# boost.net
KiCad netlist of a schematic drawn in Altium Designer
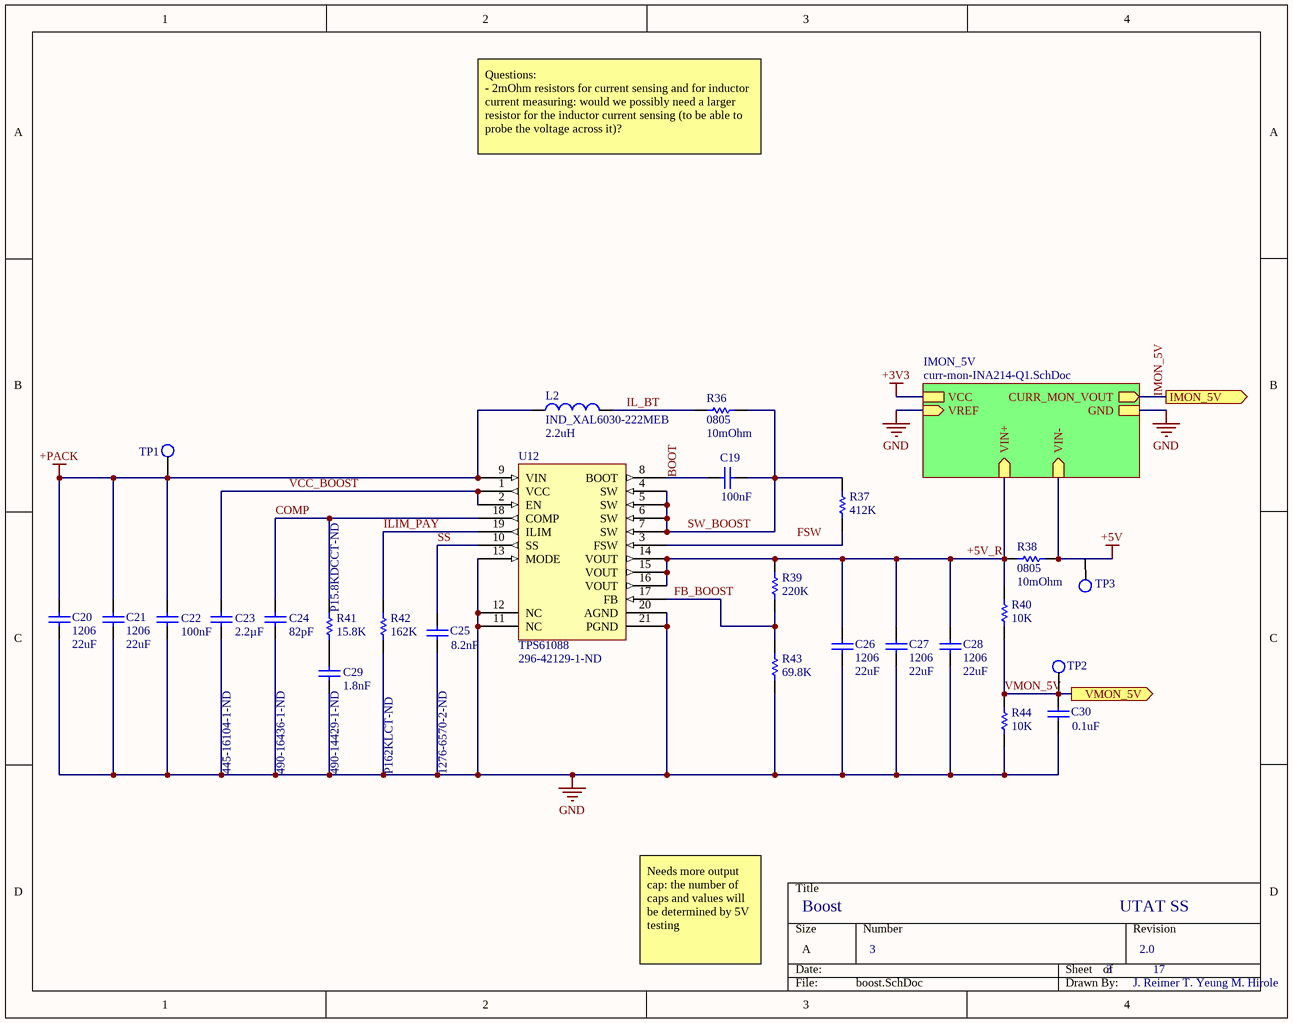
[diagram p0: boost.SchDoc]

(export (version "E")
  (design (tool "Eeschema 10.0.6"))
  (components
    (comp (ref "C19")
      (value "100nF")
      (footprint "CAP0402R")
      (description "0402 capacitor")
      (fields (field (name "Comment") "0402"))
      (libsource (lib "heron-general") (part "CAP0402"))
    )
    (comp (ref "C20")
      (value "1206")
      (footprint "CAP1206R")
      (description "1206 capacitor")
      (fields (field (name "ALTIUM_VALUE") "22uF"))
      (libsource (lib "heron-general") (part "CAP1206"))
    )
    (comp (ref "C21")
      (value "1206")
      (footprint "CAP1206R")
      (description "1206 capacitor")
      (fields (field (name "ALTIUM_VALUE") "22uF"))
      (libsource (lib "heron-general") (part "CAP1206"))
    )
    (comp (ref "C22")
      (value "100nF")
      (footprint "CAP0402R")
      (description "0402 capacitor")
      (fields (field (name "Comment") "0402"))
      (libsource (lib "heron-general") (part "CAP0402"))
    )
    (comp (ref "C23")
      (value "2.2µF")
      (footprint "CAP0603R")
      (description "0603 capacitor")
      (fields
        (field (name "SUPPLIER PART NUMBER 1") "445-16104-1-ND")
        (field (name "MANUFACTURER") "TDK")
        (field (name "MANUFACTURER PART NUMBER") "CGA3E1X7S1C225K080AC")
      )
      (libsource (lib "heron-general") (part "CAP0603"))
    )
    (comp (ref "C24")
      (value "82pF")
      (footprint "CAP0402R")
      (description "0402 capacitor")
      (fields
        (field (name "SUPPLIER PART NUMBER 1") "490-16436-1-ND")
        (field (name "MANUFACTURER") "Murata")
        (field (name "MANUFACTURER PART NUMBER") "GCM1555C1H820FA16D")
      )
      (libsource (lib "heron-general") (part "CAP0402"))
    )
    (comp (ref "C25")
      (value "8.2nF")
      (footprint "CAP0402R")
      (description "0402 capacitor")
      (fields
        (field (name "SUPPLIER PART NUMBER 1") "1276-6570-2-ND")
        (field (name "MANUFACTURER") "Samsung")
        (field (name "MANUFACTURER PART NUMBER") "CL05B822KB5VPNC")
      )
      (libsource (lib "heron-general") (part "CAP0402"))
    )
    (comp (ref "C26")
      (value "1206")
      (footprint "CAP1206R")
      (description "1206 capacitor")
      (fields (field (name "ALTIUM_VALUE") "22uF"))
      (libsource (lib "heron-general") (part "CAP1206"))
    )
    (comp (ref "C27")
      (value "1206")
      (footprint "CAP1206R")
      (description "1206 capacitor")
      (fields (field (name "ALTIUM_VALUE") "22uF"))
      (libsource (lib "heron-general") (part "CAP1206"))
    )
    (comp (ref "C28")
      (value "1206")
      (footprint "CAP1206R")
      (description "1206 capacitor")
      (fields (field (name "ALTIUM_VALUE") "22uF"))
      (libsource (lib "heron-general") (part "CAP1206"))
    )
    (comp (ref "C29")
      (value "1.8nF")
      (footprint "CAP0402R")
      (description "0402 capacitor")
      (fields
        (field (name "SUPPLIER PART NUMBER 1") "490-14429-1-ND")
        (field (name "MANUFACTURER") "Murata")
        (field (name "MANUFACTURER PART NUMBER") "GCM155R71H182KA37D")
      )
      (libsource (lib "heron-general") (part "CAP0402"))
    )
    (comp (ref "C30")
      (value "0.1uF")
      (footprint "CAP0402R")
      (description "0402 capacitor")
      (fields (field (name "Comment") "0402"))
      (libsource (lib "heron-general") (part "CAP0402"))
    )
    (comp (ref "L2")
      (value "IND_XAL6030-222MEB")
      (footprint "XAL6030-222MEB")
      (description "Inductor")
      (fields
        (field (name "MANUFACTURER") "Coilcraft")
        (field (name "MANUFACTURER PART NUMBER") "XAL6030-222MEB")
        (field (name "ALTIUM_VALUE") "2.2uH")
        (field (name "PUBLISHER") "Altium Limited")
      )
      (libsource (lib "heron-general") (part "IND_XAL6030-222MEB"))
    )
    (comp (ref "R36")
      (value "0805")
      (footprint "RES0805R")
      (description "0805 resistor")
      (fields
        (field (name "ALTIUM_VALUE") "10mOhm")
        (field (name "MANUFACTURER") "Panasonic")
        (field (name "MANUFACTURER PART NUMBER") "ERJ-8BWJR010V")
      )
      (libsource (lib "heron-general") (part "RES0805"))
    )
    (comp (ref "R37")
      (value "412K")
      (footprint "RES0402R")
      (description "0402 resistor")
      (fields (field (name "Comment") "0402"))
      (libsource (lib "heron-general") (part "RES0402"))
    )
    (comp (ref "R38")
      (value "0805")
      (footprint "RES0805R")
      (description "0805 resistor")
      (fields
        (field (name "ALTIUM_VALUE") "10mOhm")
        (field (name "MANUFACTURER") "Panasonic")
        (field (name "MANUFACTURER PART NUMBER") "ERJ-8BWJR010V")
      )
      (libsource (lib "heron-general") (part "RES0805"))
    )
    (comp (ref "R39")
      (value "220K")
      (footprint "RES0402R")
      (description "0402 resistor")
      (fields (field (name "Comment") "0402"))
      (libsource (lib "heron-general") (part "RES0402"))
    )
    (comp (ref "R40")
      (value "10K")
      (footprint "RES0402R")
      (description "0402 resistor")
      (fields (field (name "Comment") "0402"))
      (libsource (lib "heron-general") (part "RES0402"))
    )
    (comp (ref "R41")
      (value "15.8K")
      (footprint "RES0402R")
      (description "0402 resistor")
      (fields
        (field (name "SUPPLIER PART NUMBER 1") "P15.8KDCCT-ND")
        (field (name "MANUFACTURER") "Panasonic")
        (field (name "MANUFACTURER PART NUMBER") "ERA-2AEB1582X")
      )
      (libsource (lib "heron-general") (part "RES0402"))
    )
    (comp (ref "R42")
      (value "162K")
      (footprint "RES0402R")
      (description "0402 resistor")
      (fields
        (field (name "SUPPLIER PART NUMBER 1") "P162KLCT-ND")
        (field (name "MANUFACTURER") "Panasonic")
        (field (name "MANUFACTURER PART NUMBER") "ERJ-2RKF1623X")
      )
      (libsource (lib "heron-general") (part "RES0402"))
    )
    (comp (ref "R43")
      (value "69.8K")
      (footprint "RES0402R")
      (description "0402 resistor")
      (fields (field (name "Comment") "0402"))
      (libsource (lib "heron-general") (part "RES0402"))
    )
    (comp (ref "R44")
      (value "10K")
      (footprint "RES0402R")
      (description "0402 resistor")
      (fields (field (name "Comment") "0402"))
      (libsource (lib "heron-general") (part "RES0402"))
    )
    (comp (ref "U12")
      (value "TPS61088")
      (footprint "QFN50P450X350X100-21N")
      (description "Boost converter")
      (fields (field (name "SUPPLIER PART NUMBER 1") "296-42129-1-ND"))
      (libsource (lib "heron-general") (part "TPS61088"))
    )
  )
  (nets
    (net (code "2") (name "+5V") (class "Default")
      (node (ref "R38") (pin "2") (pinfunction "2_2") (pintype "passive"))
    )
    (net (code "3") (name "+PACK") (class "Default")
      (node (ref "C20") (pin "2") (pinfunction "2_2") (pintype "passive"))
      (node (ref "C21") (pin "2") (pinfunction "2_2") (pintype "passive"))
      (node (ref "C22") (pin "2") (pinfunction "2_2") (pintype "passive"))
      (node (ref "L2") (pin "1") (pinfunction "1_1") (pintype "passive"))
      (node (ref "U12") (pin "9") (pinfunction "VIN_9") (pintype "input"))
    )
    (net (code "4") (name "/+5V_R") (class "Default")
      (node (ref "C26") (pin "2") (pinfunction "2_2") (pintype "passive"))
      (node (ref "C27") (pin "2") (pinfunction "2_2") (pintype "passive"))
      (node (ref "C28") (pin "2") (pinfunction "2_2") (pintype "passive"))
      (node (ref "R38") (pin "1") (pinfunction "1_1") (pintype "passive"))
      (node (ref "R39") (pin "2") (pinfunction "2_2") (pintype "passive"))
      (node (ref "R40") (pin "2") (pinfunction "2_2") (pintype "passive"))
      (node (ref "U12") (pin "14") (pinfunction "VOUT_14") (pintype "output"))
      (node (ref "U12") (pin "15") (pinfunction "VOUT_15") (pintype "output"))
      (node (ref "U12") (pin "16") (pinfunction "VOUT_16") (pintype "output"))
    )
    (net (code "5") (name "/BOOT") (class "Default")
      (node (ref "C19") (pin "2") (pinfunction "2_2") (pintype "passive"))
      (node (ref "U12") (pin "8") (pinfunction "BOOT_8") (pintype "output"))
    )
    (net (code "6") (name "/COMP") (class "Default")
      (node (ref "C24") (pin "2") (pinfunction "2_2") (pintype "passive"))
      (node (ref "R41") (pin "2") (pinfunction "2_2") (pintype "passive"))
      (node (ref "U12") (pin "18") (pinfunction "COMP_18") (pintype "output"))
    )
    (net (code "7") (name "/FB_BOOST") (class "Default")
      (node (ref "R39") (pin "1") (pinfunction "1_1") (pintype "passive"))
      (node (ref "R43") (pin "2") (pinfunction "2_2") (pintype "passive"))
      (node (ref "U12") (pin "17") (pinfunction "FB_17") (pintype "input"))
    )
    (net (code "9") (name "/ILIM_PAY") (class "Default")
      (node (ref "R42") (pin "2") (pinfunction "2_2") (pintype "passive"))
      (node (ref "U12") (pin "19") (pinfunction "ILIM_19") (pintype "output"))
    )
    (net (code "10") (name "/IL_BT") (class "Default")
      (node (ref "L2") (pin "2") (pinfunction "2_2") (pintype "passive"))
      (node (ref "R36") (pin "1") (pinfunction "1_1") (pintype "passive"))
    )
    (net (code "12") (name "/SS") (class "Default")
      (node (ref "C25") (pin "2") (pinfunction "2_2") (pintype "passive"))
      (node (ref "U12") (pin "10") (pinfunction "SS_10") (pintype "output"))
    )
    (net (code "13") (name "/SW_BOOST") (class "Default")
      (node (ref "C19") (pin "1") (pinfunction "1_1") (pintype "passive"))
      (node (ref "R36") (pin "2") (pinfunction "2_2") (pintype "passive"))
      (node (ref "R37") (pin "1") (pinfunction "1_1") (pintype "passive"))
      (node (ref "U12") (pin "4") (pinfunction "SW_4") (pintype "input"))
      (node (ref "U12") (pin "5") (pinfunction "SW_5") (pintype "input"))
      (node (ref "U12") (pin "6") (pinfunction "SW_6") (pintype "input"))
      (node (ref "U12") (pin "7") (pinfunction "SW_7") (pintype "input"))
    )
    (net (code "14") (name "/VCC_BOOST") (class "Default")
      (node (ref "C23") (pin "2") (pinfunction "2_2") (pintype "passive"))
      (node (ref "U12") (pin "1") (pinfunction "VCC_1") (pintype "output"))
      (node (ref "U12") (pin "2") (pinfunction "EN_2") (pintype "input"))
    )
    (net (code "15") (name "/VMON_5V") (class "Default")
      (node (ref "C30") (pin "1") (pinfunction "1_1") (pintype "passive"))
      (node (ref "R40") (pin "1") (pinfunction "1_1") (pintype "passive"))
      (node (ref "R44") (pin "2") (pinfunction "2_2") (pintype "passive"))
    )
    (net (code "16") (name "GND") (class "Default")
      (node (ref "C20") (pin "1") (pinfunction "1_1") (pintype "passive"))
      (node (ref "C21") (pin "1") (pinfunction "1_1") (pintype "passive"))
      (node (ref "C22") (pin "1") (pinfunction "1_1") (pintype "passive"))
      (node (ref "C23") (pin "1") (pinfunction "1_1") (pintype "passive"))
      (node (ref "C24") (pin "1") (pinfunction "1_1") (pintype "passive"))
      (node (ref "C25") (pin "1") (pinfunction "1_1") (pintype "passive"))
      (node (ref "C26") (pin "1") (pinfunction "1_1") (pintype "passive"))
      (node (ref "C27") (pin "1") (pinfunction "1_1") (pintype "passive"))
      (node (ref "C28") (pin "1") (pinfunction "1_1") (pintype "passive"))
      (node (ref "C29") (pin "1") (pinfunction "1_1") (pintype "passive"))
      (node (ref "C30") (pin "2") (pinfunction "2_2") (pintype "passive"))
      (node (ref "R42") (pin "1") (pinfunction "1_1") (pintype "passive"))
      (node (ref "R43") (pin "1") (pinfunction "1_1") (pintype "passive"))
      (node (ref "R44") (pin "1") (pinfunction "1_1") (pintype "passive"))
      (node (ref "U12") (pin "11") (pinfunction "NC_11") (pintype "passive"))
      (node (ref "U12") (pin "12") (pinfunction "NC_12") (pintype "passive"))
      (node (ref "U12") (pin "13") (pinfunction "MODE_13") (pintype "input"))
      (node (ref "U12") (pin "20") (pinfunction "AGND_20") (pintype "power_in"))
      (node (ref "U12") (pin "21") (pinfunction "PGND_21") (pintype "power_in"))
    )
    (net (code "17") (name "Net-(C29-Pad2)") (class "Default")
      (node (ref "C29") (pin "2") (pinfunction "2_2") (pintype "passive"))
      (node (ref "R41") (pin "1") (pinfunction "1_1") (pintype "passive"))
    )
    (net (code "18") (name "Net-(U12-FSW)") (class "Default")
      (node (ref "R37") (pin "2") (pinfunction "2_2") (pintype "passive"))
      (node (ref "U12") (pin "3") (pinfunction "FSW_3") (pintype "input"))
    )
  )
)
